# ESP32-Cam.net
KiCad netlist of a schematic drawn in Altium Designer
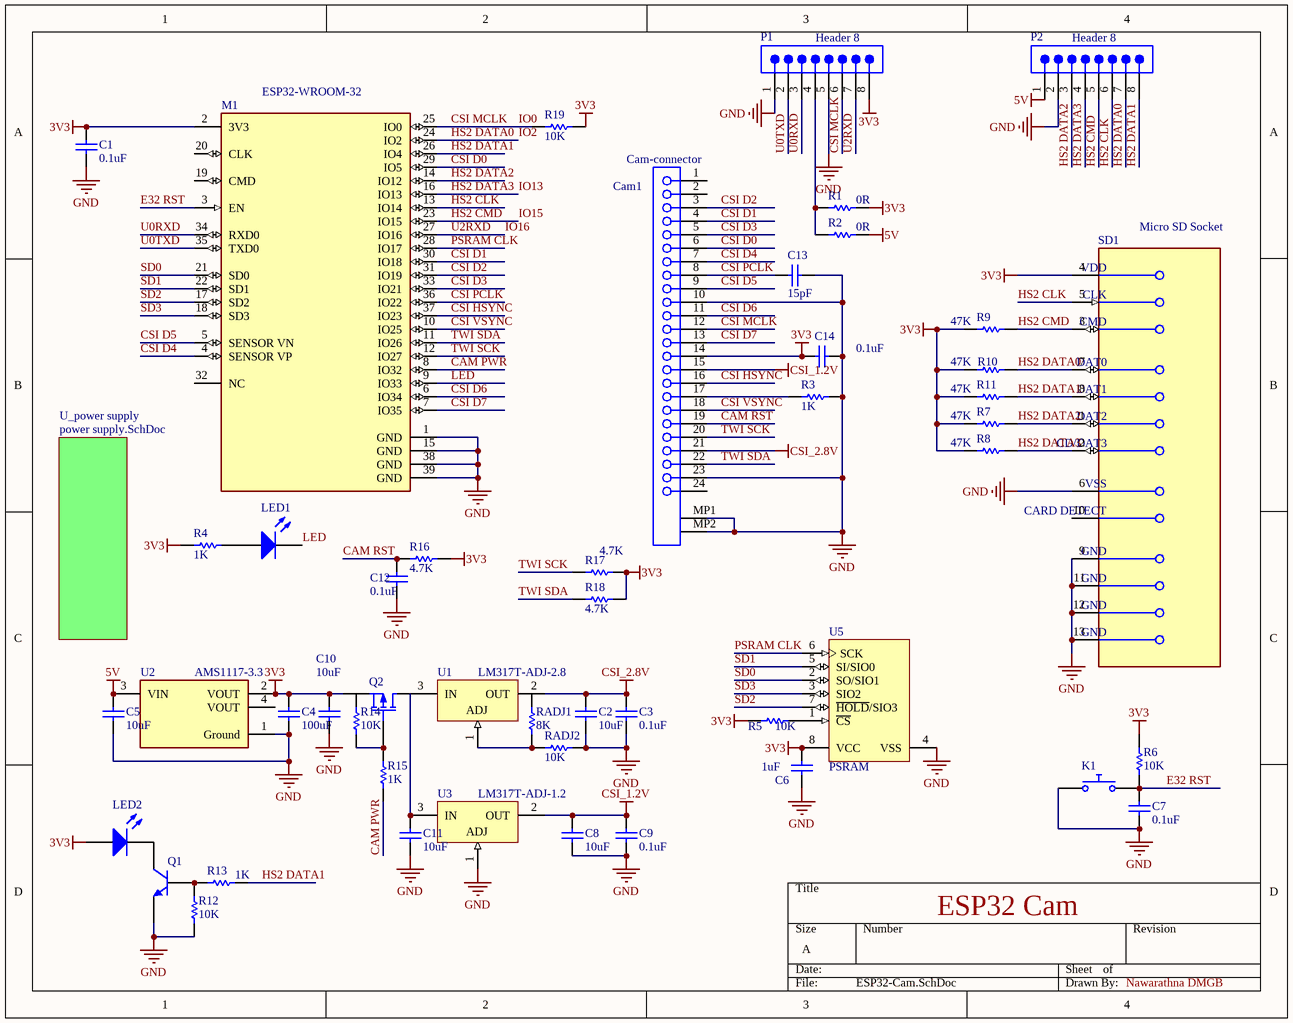
[diagram p0: ESP32-Cam.SchDoc]

(export (version "E")
  (design (tool "Eeschema 10.0.6"))
  (components
    (comp (ref "C1")
      (value "0.1uF")
      (description "Capacitor")
      (libsource (lib "Simulation Generic Components") (part "Capacitor"))
    )
    (comp (ref "C2")
      (value "10uF")
      (description "Capacitor")
      (libsource (lib "Simulation Generic Components") (part "Capacitor"))
    )
    (comp (ref "C3")
      (value "0.1uF")
      (description "Capacitor")
      (libsource (lib "Simulation Generic Components") (part "Capacitor"))
    )
    (comp (ref "C4")
      (value "100uF")
      (description "Capacitor")
      (libsource (lib "Simulation Generic Components") (part "Capacitor"))
    )
    (comp (ref "C5")
      (value "10uF")
      (description "Capacitor")
      (libsource (lib "Simulation Generic Components") (part "Capacitor"))
    )
    (comp (ref "C6")
      (value "1uF")
      (description "Capacitor")
      (libsource (lib "Simulation Generic Components") (part "Capacitor"))
    )
    (comp (ref "C7")
      (value "0.1uF")
      (description "Capacitor")
      (libsource (lib "Simulation Generic Components") (part "Capacitor"))
    )
    (comp (ref "C8")
      (value "10uF")
      (description "Capacitor")
      (libsource (lib "Simulation Generic Components") (part "Capacitor"))
    )
    (comp (ref "C9")
      (value "0.1uF")
      (description "Capacitor")
      (libsource (lib "Simulation Generic Components") (part "Capacitor"))
    )
    (comp (ref "C10")
      (value "10uF")
      (description "Capacitor")
      (libsource (lib "Simulation Generic Components") (part "Capacitor"))
    )
    (comp (ref "C11")
      (value "10uF")
      (description "Capacitor")
      (libsource (lib "Simulation Generic Components") (part "Capacitor"))
    )
    (comp (ref "C12")
      (value "0.1uF")
      (description "Capacitor")
      (libsource (lib "Simulation Generic Components") (part "Capacitor"))
    )
    (comp (ref "C13")
      (value "15pF")
      (description "Capacitor")
      (libsource (lib "Simulation Generic Components") (part "Capacitor"))
    )
    (comp (ref "C14")
      (value "0.1uF")
      (description "Capacitor")
      (libsource (lib "Simulation Generic Components") (part "Capacitor"))
    )
    (comp (ref "Cam1")
      (value "Cam-connector")
      (footprint "MOLX-52435-2471")
      (fields (field (name "PARTNUMBER") "52435-2471") (field (name "MANUFACTURER") "Molex"))
      (libsource (lib "Altium Content Vault") (part "MOLX-52435-2471"))
    )
    (comp (ref "K1")
      (value "Push Button Normally Opened")
      (libsource (lib "Simulation Generic Components") (part "Push Button NO"))
    )
    (comp (ref "LED1")
      (value "Light-Emitting Diode")
      (libsource (lib "Simulation Generic Components") (part "LED"))
    )
    (comp (ref "LED2")
      (value "Light-Emitting Diode")
      (libsource (lib "Simulation Generic Components") (part "LED"))
    )
    (comp (ref "M1")
      (value "ESP32-WROOM-32")
      (footprint "FP-ESP32-WROOM-32-MFG")
      (description "RX TXRX MOD WIFI SURFACE MOUNT")
      (libsource (lib "Altium Content Vault") (part "ee866abf0b6c51247b7f5cdebf2f250"))
    )
    (comp (ref "P1")
      (value "Header 8")
      (footprint "66200811122")
      (libsource (lib "Altium Content Vault") (part "Header_Male_1R_08P"))
    )
    (comp (ref "P2")
      (value "Header 8")
      (footprint "66200811122")
      (libsource (lib "Altium Content Vault") (part "Header_Male_1R_08P"))
    )
    (comp (ref "Q1")
      (value "Bipolar NPN 3 Pins Transistor Gummel-Poon Model")
      (libsource (lib "Simulation Generic Components") (part "BJT NPN_GP"))
    )
    (comp (ref "Q2")
      (value "P-channel Power MOSFET VDMOS Model")
      (libsource (lib "Simulation Generic Components") (part "MOSFET P-ch VDMOS"))
    )
    (comp (ref "R1")
      (value "0R")
      (description "Resistor")
      (libsource (lib "Simulation Generic Components") (part "Resistor"))
    )
    (comp (ref "R2")
      (value "0R")
      (description "Resistor")
      (libsource (lib "Simulation Generic Components") (part "Resistor"))
    )
    (comp (ref "R3")
      (value "1K")
      (description "Resistor")
      (libsource (lib "Simulation Generic Components") (part "Resistor"))
    )
    (comp (ref "R4")
      (value "1K")
      (description "Resistor")
      (libsource (lib "Simulation Generic Components") (part "Resistor"))
    )
    (comp (ref "R5")
      (value "10K")
      (description "Resistor")
      (libsource (lib "Simulation Generic Components") (part "Resistor"))
    )
    (comp (ref "R6")
      (value "10K")
      (description "Resistor")
      (libsource (lib "Simulation Generic Components") (part "Resistor"))
    )
    (comp (ref "R7")
      (value "47K")
      (description "Resistor")
      (libsource (lib "Simulation Generic Components") (part "Resistor"))
    )
    (comp (ref "R8")
      (value "47K")
      (description "Resistor")
      (libsource (lib "Simulation Generic Components") (part "Resistor"))
    )
    (comp (ref "R9")
      (value "47K")
      (description "Resistor")
      (libsource (lib "Simulation Generic Components") (part "Resistor"))
    )
    (comp (ref "R10")
      (value "47K")
      (description "Resistor")
      (libsource (lib "Simulation Generic Components") (part "Resistor"))
    )
    (comp (ref "R11")
      (value "47K")
      (description "Resistor")
      (libsource (lib "Simulation Generic Components") (part "Resistor"))
    )
    (comp (ref "R12")
      (value "10K")
      (description "Resistor")
      (libsource (lib "Simulation Generic Components") (part "Resistor"))
    )
    (comp (ref "R13")
      (value "1K")
      (description "Resistor")
      (libsource (lib "Simulation Generic Components") (part "Resistor"))
    )
    (comp (ref "R14")
      (value "10K")
      (description "Resistor")
      (libsource (lib "Simulation Generic Components") (part "Resistor"))
    )
    (comp (ref "R15")
      (value "1K")
      (description "Resistor")
      (libsource (lib "Simulation Generic Components") (part "Resistor"))
    )
    (comp (ref "R16")
      (value "4.7K")
      (description "Resistor")
      (libsource (lib "Simulation Generic Components") (part "Resistor"))
    )
    (comp (ref "R17")
      (value "4.7K")
      (description "Resistor")
      (libsource (lib "Simulation Generic Components") (part "Resistor"))
    )
    (comp (ref "R18")
      (value "4.7K")
      (description "Resistor")
      (libsource (lib "Simulation Generic Components") (part "Resistor"))
    )
    (comp (ref "R19")
      (value "10K")
      (description "Resistor")
      (libsource (lib "Simulation Generic Components") (part "Resistor"))
    )
    (comp (ref "RADJ1")
      (value "8K")
      (description "Resistor")
      (libsource (lib "Simulation Generic Components") (part "Resistor"))
    )
    (comp (ref "RADJ2")
      (value "10K")
      (description "Resistor")
      (libsource (lib "Simulation Generic Components") (part "Resistor"))
    )
    (comp (ref "SD1")
      (value "Micro SD Socket")
      (footprint "FP-DM3CS-SF-MFG")
      (description "CONN MICRO SD CARD HINGED TYPE")
      (libsource (lib "Altium Content Vault") (part "bac915de5305cfdd1ca301aae530106"))
    )
    (comp (ref "U1")
      (value "LM317T-ADJ-2.8")
      (footprint "TO-220")
      (description "1.5A, 1.2V to 37V Adjustable Voltage Regulator, 3-Pin TO-220")
      (libsource (lib "Altium Content Vault") (part "PM-REG-117-SIL3"))
    )
    (comp (ref "U2")
      (value "AMS1117-3.3")
      (footprint "FP-AMS1117-IPC_C")
      (description "LDO Voltage Regulators 1A, 3.3V")
      (fields
        (field (name "OCTOPART") "https://octopart.com/ams1117-3.3-advanced+monolithic+systems-25899300")
        (field (name "MANUFACTURER") "Advanced Monolithic Systems")
      )
      (libsource (lib "Altium Content Vault") (part "8bdbb5f8e77002000e30dd2845d0354"))
    )
    (comp (ref "U3")
      (value "LM317T-ADJ-1.2")
      (footprint "TO-220")
      (description "1.5A, 1.2V to 37V Adjustable Voltage Regulator, 3-Pin TO-220")
      (libsource (lib "Altium Content Vault") (part "PM-REG-117-SIL3"))
    )
    (comp (ref "U5")
      (value "PSRAM")
      (footprint "MCHP-SOIC-SN8_N")
      (fields (field (name "MANUFACTURER") "Microchip") (field (name "PARTNUMBER") "23LC512-I/SN"))
      (libsource (lib "Altium Content Vault") (part "MCHP-23A1024_512-LC1024_512-8"))
    )
  )
  (nets
    (net (code "1") (name "/CAM PWR") (class "Default")
      (node (ref "M1") (pin "8") (pinfunction "IO32_8") (pintype "bidirectional"))
      (node (ref "R15") (pin "2") (pinfunction "2_2") (pintype "passive"))
    )
    (net (code "2") (name "/CAM RST") (class "Default")
      (node (ref "C12") (pin "1") (pinfunction "1_1") (pintype "passive"))
      (node (ref "Cam1") (pin "19") (pinfunction "19_19") (pintype "passive"))
      (node (ref "R16") (pin "1") (pinfunction "1_1") (pintype "passive"))
    )
    (net (code "3") (name "/CSI D0") (class "Default")
      (node (ref "Cam1") (pin "6") (pinfunction "6_6") (pintype "passive"))
      (node (ref "M1") (pin "29") (pinfunction "IO5_29") (pintype "bidirectional"))
    )
    (net (code "4") (name "/CSI D1") (class "Default")
      (node (ref "Cam1") (pin "4") (pinfunction "4_4") (pintype "passive"))
      (node (ref "M1") (pin "30") (pinfunction "IO18_30") (pintype "bidirectional"))
    )
    (net (code "5") (name "/CSI D2") (class "Default")
      (node (ref "Cam1") (pin "3") (pinfunction "3_3") (pintype "passive"))
      (node (ref "M1") (pin "31") (pinfunction "IO19_31") (pintype "bidirectional"))
    )
    (net (code "6") (name "/CSI D3") (class "Default")
      (node (ref "Cam1") (pin "5") (pinfunction "5_5") (pintype "passive"))
      (node (ref "M1") (pin "33") (pinfunction "IO21_33") (pintype "bidirectional"))
    )
    (net (code "7") (name "/CSI D4") (class "Default")
      (node (ref "Cam1") (pin "7") (pinfunction "7_7") (pintype "passive"))
      (node (ref "M1") (pin "4") (pinfunction "SENSOR_VP_4") (pintype "bidirectional"))
    )
    (net (code "8") (name "/CSI D5") (class "Default")
      (node (ref "Cam1") (pin "9") (pinfunction "9_9") (pintype "passive"))
      (node (ref "M1") (pin "5") (pinfunction "SENSOR_VN_5") (pintype "bidirectional"))
    )
    (net (code "9") (name "/CSI D6") (class "Default")
      (node (ref "Cam1") (pin "11") (pinfunction "11_11") (pintype "passive"))
      (node (ref "M1") (pin "6") (pinfunction "IO34_6") (pintype "bidirectional"))
    )
    (net (code "10") (name "/CSI D7") (class "Default")
      (node (ref "Cam1") (pin "13") (pinfunction "13_13") (pintype "passive"))
      (node (ref "M1") (pin "7") (pinfunction "IO35_7") (pintype "bidirectional"))
    )
    (net (code "11") (name "/CSI HSYNC") (class "Default")
      (node (ref "Cam1") (pin "16") (pinfunction "16_16") (pintype "passive"))
      (node (ref "M1") (pin "37") (pinfunction "IO23_37") (pintype "bidirectional"))
    )
    (net (code "12") (name "/CSI MCLK") (class "Default")
      (node (ref "Cam1") (pin "12") (pinfunction "12_12") (pintype "passive"))
      (node (ref "M1") (pin "25") (pinfunction "IO0_25") (pintype "bidirectional"))
      (node (ref "P1") (pin "6") (pinfunction "6_6") (pintype "passive"))
      (node (ref "R19") (pin "1") (pinfunction "1_1") (pintype "passive"))
    )
    (net (code "13") (name "/CSI PCLK") (class "Default")
      (node (ref "C13") (pin "1") (pinfunction "1_1") (pintype "passive"))
      (node (ref "Cam1") (pin "8") (pinfunction "8_8") (pintype "passive"))
      (node (ref "M1") (pin "36") (pinfunction "IO22_36") (pintype "bidirectional"))
    )
    (net (code "14") (name "/CSI VSYNC") (class "Default")
      (node (ref "Cam1") (pin "18") (pinfunction "18_18") (pintype "passive"))
      (node (ref "M1") (pin "10") (pinfunction "IO25_10") (pintype "bidirectional"))
    )
    (net (code "15") (name "/E32 RST") (class "Default")
      (node (ref "C7") (pin "1") (pinfunction "1_1") (pintype "passive"))
      (node (ref "K1") (pin "2") (pinfunction "2_2") (pintype "passive"))
      (node (ref "M1") (pin "3") (pinfunction "EN_3") (pintype "input"))
      (node (ref "R6") (pin "2") (pinfunction "2_2") (pintype "passive"))
    )
    (net (code "16") (name "/HS2 CLK") (class "Default")
      (node (ref "M1") (pin "13") (pinfunction "IO14_13") (pintype "bidirectional"))
      (node (ref "P2") (pin "6") (pinfunction "6_6") (pintype "passive"))
      (node (ref "SD1") (pin "5") (pinfunction "CLK_5") (pintype "input"))
    )
    (net (code "17") (name "/HS2 CMD") (class "Default")
      (node (ref "M1") (pin "23") (pinfunction "IO15_23") (pintype "bidirectional"))
      (node (ref "P2") (pin "5") (pinfunction "5_5") (pintype "passive"))
      (node (ref "R9") (pin "2") (pinfunction "2_2") (pintype "passive"))
      (node (ref "SD1") (pin "3") (pinfunction "CMD_3") (pintype "bidirectional"))
    )
    (net (code "18") (name "/HS2 DATA0") (class "Default")
      (node (ref "M1") (pin "24") (pinfunction "IO2_24") (pintype "bidirectional"))
      (node (ref "P2") (pin "7") (pinfunction "7_7") (pintype "passive"))
      (node (ref "R10") (pin "2") (pinfunction "2_2") (pintype "passive"))
      (node (ref "SD1") (pin "7") (pinfunction "DAT0_7") (pintype "bidirectional"))
    )
    (net (code "19") (name "/HS2 DATA1") (class "Default")
      (node (ref "M1") (pin "26") (pinfunction "IO4_26") (pintype "bidirectional"))
      (node (ref "P2") (pin "8") (pinfunction "8_8") (pintype "passive"))
      (node (ref "R11") (pin "2") (pinfunction "2_2") (pintype "passive"))
      (node (ref "R13") (pin "1") (pinfunction "1_1") (pintype "passive"))
      (node (ref "SD1") (pin "8") (pinfunction "DAT1_8") (pintype "bidirectional"))
    )
    (net (code "20") (name "/HS2 DATA2") (class "Default")
      (node (ref "M1") (pin "14") (pinfunction "IO12_14") (pintype "bidirectional"))
      (node (ref "P2") (pin "3") (pinfunction "3_3") (pintype "passive"))
      (node (ref "R7") (pin "2") (pinfunction "2_2") (pintype "passive"))
      (node (ref "SD1") (pin "1") (pinfunction "DAT2_1") (pintype "bidirectional"))
    )
    (net (code "21") (name "/HS2 DATA3") (class "Default")
      (node (ref "M1") (pin "16") (pinfunction "IO13_16") (pintype "bidirectional"))
      (node (ref "P2") (pin "4") (pinfunction "4_4") (pintype "passive"))
      (node (ref "R8") (pin "2") (pinfunction "2_2") (pintype "passive"))
      (node (ref "SD1") (pin "2") (pinfunction "CD/DAT3_2") (pintype "bidirectional"))
    )
    (net (code "22") (name "/IO16") (class "Default")
      (node (ref "M1") (pin "27") (pinfunction "IO16_27") (pintype "bidirectional"))
      (node (ref "P1") (pin "7") (pinfunction "7_7") (pintype "passive"))
    )
    (net (code "23") (name "/LED") (class "Default")
      (node (ref "LED1") (pin "2") (pinfunction "K_2") (pintype "passive"))
      (node (ref "M1") (pin "9") (pinfunction "IO33_9") (pintype "bidirectional"))
    )
    (net (code "24") (name "/PSRAM CLK") (class "Default")
      (node (ref "M1") (pin "28") (pinfunction "IO17_28") (pintype "bidirectional"))
      (node (ref "U5") (pin "6") (pinfunction "SCK_6") (pintype "input"))
    )
    (net (code "25") (name "/SD0") (class "Default")
      (node (ref "M1") (pin "21") (pinfunction "SD0_21") (pintype "bidirectional"))
      (node (ref "U5") (pin "2") (pinfunction "SO/SIO1_2") (pintype "bidirectional"))
    )
    (net (code "26") (name "/SD1") (class "Default")
      (node (ref "M1") (pin "22") (pinfunction "SD1_22") (pintype "bidirectional"))
      (node (ref "U5") (pin "5") (pinfunction "SI/SIO0_5") (pintype "bidirectional"))
    )
    (net (code "27") (name "/SD2") (class "Default")
      (node (ref "M1") (pin "17") (pinfunction "SD2_17") (pintype "bidirectional"))
      (node (ref "U5") (pin "7") (pinfunction "~{HOLD}/SIO3_7") (pintype "bidirectional"))
    )
    (net (code "28") (name "/SD3") (class "Default")
      (node (ref "M1") (pin "18") (pinfunction "SD3_18") (pintype "bidirectional"))
      (node (ref "U5") (pin "3") (pinfunction "SIO2_3") (pintype "bidirectional"))
    )
    (net (code "29") (name "/TWI SCK") (class "Default")
      (node (ref "Cam1") (pin "20") (pinfunction "20_20") (pintype "passive"))
      (node (ref "M1") (pin "12") (pinfunction "IO27_12") (pintype "bidirectional"))
      (node (ref "R17") (pin "1") (pinfunction "1_1") (pintype "passive"))
    )
    (net (code "30") (name "/TWI SDA") (class "Default")
      (node (ref "Cam1") (pin "22") (pinfunction "22_22") (pintype "passive"))
      (node (ref "M1") (pin "11") (pinfunction "IO26_11") (pintype "bidirectional"))
      (node (ref "R18") (pin "1") (pinfunction "1_1") (pintype "passive"))
    )
    (net (code "31") (name "/U0RXD") (class "Default")
      (node (ref "M1") (pin "34") (pinfunction "RXD0_34") (pintype "bidirectional"))
      (node (ref "P1") (pin "3") (pinfunction "3_3") (pintype "passive"))
    )
    (net (code "32") (name "/U0TXD") (class "Default")
      (node (ref "M1") (pin "35") (pinfunction "TXD0_35") (pintype "bidirectional"))
      (node (ref "P1") (pin "2") (pinfunction "2_2") (pintype "passive"))
    )
    (net (code "33") (name "3V3") (class "Default")
      (node (ref "C1") (pin "1") (pinfunction "1_1") (pintype "passive"))
      (node (ref "C10") (pin "1") (pinfunction "1_1") (pintype "passive"))
      (node (ref "C14") (pin "1") (pinfunction "1_1") (pintype "passive"))
      (node (ref "C4") (pin "1") (pinfunction "1_1") (pintype "passive"))
      (node (ref "C6") (pin "1") (pinfunction "1_1") (pintype "passive"))
      (node (ref "Cam1") (pin "14") (pinfunction "14_14") (pintype "passive"))
      (node (ref "LED2") (pin "1") (pinfunction "A_1") (pintype "passive"))
      (node (ref "M1") (pin "2") (pinfunction "3V3_2") (pintype "power_in"))
      (node (ref "P1") (pin "8") (pinfunction "8_8") (pintype "passive"))
      (node (ref "Q2") (pin "3") (pinfunction "S_3") (pintype "passive"))
      (node (ref "R1") (pin "1") (pinfunction "1_1") (pintype "passive"))
      (node (ref "R10") (pin "1") (pinfunction "1_1") (pintype "passive"))
      (node (ref "R11") (pin "1") (pinfunction "1_1") (pintype "passive"))
      (node (ref "R16") (pin "2") (pinfunction "2_2") (pintype "passive"))
      (node (ref "R17") (pin "2") (pinfunction "2_2") (pintype "passive"))
      (node (ref "R18") (pin "2") (pinfunction "2_2") (pintype "passive"))
      (node (ref "R19") (pin "2") (pinfunction "2_2") (pintype "passive"))
      (node (ref "R4") (pin "1") (pinfunction "1_1") (pintype "passive"))
      (node (ref "R5") (pin "1") (pinfunction "1_1") (pintype "passive"))
      (node (ref "R6") (pin "1") (pinfunction "1_1") (pintype "passive"))
      (node (ref "R7") (pin "1") (pinfunction "1_1") (pintype "passive"))
      (node (ref "R8") (pin "1") (pinfunction "1_1") (pintype "passive"))
      (node (ref "R9") (pin "1") (pinfunction "1_1") (pintype "passive"))
      (node (ref "SD1") (pin "4") (pinfunction "VDD_4") (pintype "power_in"))
      (node (ref "U2") (pin "2") (pinfunction "VOUT_2") (pintype "passive"))
      (node (ref "U5") (pin "8") (pinfunction "VCC_8") (pintype "power_in"))
    )
    (net (code "34") (name "5V") (class "Default")
      (node (ref "C5") (pin "1") (pinfunction "1_1") (pintype "passive"))
      (node (ref "P2") (pin "1") (pinfunction "1_1") (pintype "passive"))
      (node (ref "R2") (pin "1") (pinfunction "1_1") (pintype "passive"))
      (node (ref "U2") (pin "3") (pinfunction "VIN_3") (pintype "power_in"))
    )
    (net (code "35") (name "CSI_1.2V") (class "Default")
      (node (ref "C8") (pin "1") (pinfunction "1_1") (pintype "passive"))
      (node (ref "C9") (pin "1") (pinfunction "1_1") (pintype "passive"))
      (node (ref "Cam1") (pin "15") (pinfunction "15_15") (pintype "passive"))
      (node (ref "U3") (pin "2") (pinfunction "OUT_2") (pintype "power_in"))
    )
    (net (code "36") (name "CSI_2.8V") (class "Default")
      (node (ref "C2") (pin "1") (pinfunction "1_1") (pintype "passive"))
      (node (ref "C3") (pin "1") (pinfunction "1_1") (pintype "passive"))
      (node (ref "Cam1") (pin "21") (pinfunction "21_21") (pintype "passive"))
      (node (ref "U1") (pin "2") (pinfunction "OUT_2") (pintype "power_in"))
    )
    (net (code "37") (name "GND") (class "Default")
      (node (ref "C1") (pin "2") (pinfunction "2_2") (pintype "passive"))
      (node (ref "C10") (pin "2") (pinfunction "2_2") (pintype "passive"))
      (node (ref "C11") (pin "2") (pinfunction "2_2") (pintype "passive"))
      (node (ref "C12") (pin "2") (pinfunction "2_2") (pintype "passive"))
      (node (ref "C13") (pin "2") (pinfunction "2_2") (pintype "passive"))
      (node (ref "C14") (pin "2") (pinfunction "2_2") (pintype "passive"))
      (node (ref "C2") (pin "2") (pinfunction "2_2") (pintype "passive"))
      (node (ref "C3") (pin "2") (pinfunction "2_2") (pintype "passive"))
      (node (ref "C4") (pin "2") (pinfunction "2_2") (pintype "passive"))
      (node (ref "C5") (pin "2") (pinfunction "2_2") (pintype "passive"))
      (node (ref "C6") (pin "2") (pinfunction "2_2") (pintype "passive"))
      (node (ref "C7") (pin "2") (pinfunction "2_2") (pintype "passive"))
      (node (ref "C8") (pin "2") (pinfunction "2_2") (pintype "passive"))
      (node (ref "C9") (pin "2") (pinfunction "2_2") (pintype "passive"))
      (node (ref "Cam1") (pin "10") (pinfunction "10_10") (pintype "passive"))
      (node (ref "Cam1") (pin "23") (pinfunction "23_23") (pintype "passive"))
      (node (ref "Cam1") (pin "MP1") (pinfunction "MP1_MP1") (pintype "passive"))
      (node (ref "Cam1") (pin "MP2") (pinfunction "MP2_MP2") (pintype "passive"))
      (node (ref "K1") (pin "1") (pinfunction "1_1") (pintype "passive"))
      (node (ref "M1") (pin "1") (pinfunction "GND_1") (pintype "power_in"))
      (node (ref "M1") (pin "15") (pinfunction "GND_15") (pintype "power_in"))
      (node (ref "M1") (pin "38") (pinfunction "GND_38") (pintype "power_in"))
      (node (ref "M1") (pin "39") (pinfunction "GND_39") (pintype "power_in"))
      (node (ref "P1") (pin "1") (pinfunction "1_1") (pintype "passive"))
      (node (ref "P1") (pin "5") (pinfunction "5_5") (pintype "passive"))
      (node (ref "P2") (pin "2") (pinfunction "2_2") (pintype "passive"))
      (node (ref "Q1") (pin "3") (pinfunction "E_3") (pintype "passive"))
      (node (ref "R12") (pin "2") (pinfunction "2_2") (pintype "passive"))
      (node (ref "R3") (pin "2") (pinfunction "2_2") (pintype "passive"))
      (node (ref "RADJ2") (pin "2") (pinfunction "2_2") (pintype "passive"))
      (node (ref "SD1") (pin "11") (pinfunction "GND_11") (pintype "power_in"))
      (node (ref "SD1") (pin "12") (pinfunction "GND_12") (pintype "power_in"))
      (node (ref "SD1") (pin "13") (pinfunction "GND_13") (pintype "power_in"))
      (node (ref "SD1") (pin "6") (pinfunction "VSS_6") (pintype "power_in"))
      (node (ref "SD1") (pin "9") (pinfunction "GND_9") (pintype "power_in"))
      (node (ref "U2") (pin "1") (pinfunction "Ground_1") (pintype "power_in"))
      (node (ref "U3") (pin "1") (pinfunction "ADJ_1") (pintype "input"))
      (node (ref "U5") (pin "4") (pinfunction "VSS_4") (pintype "power_in"))
    )
    (net (code "38") (name "Net-(Cam1-Pad17)") (class "Default")
      (node (ref "Cam1") (pin "17") (pinfunction "17_17") (pintype "passive"))
      (node (ref "R3") (pin "1") (pinfunction "1_1") (pintype "passive"))
    )
    (net (code "39") (name "Net-(LED1-A)") (class "Default")
      (node (ref "LED1") (pin "1") (pinfunction "A_1") (pintype "passive"))
      (node (ref "R4") (pin "2") (pinfunction "2_2") (pintype "passive"))
    )
    (net (code "40") (name "Net-(LED2-K)") (class "Default")
      (node (ref "LED2") (pin "2") (pinfunction "K_2") (pintype "passive"))
      (node (ref "Q1") (pin "1") (pinfunction "C_1") (pintype "passive"))
    )
    (net (code "41") (name "Net-(P1-Pad4)") (class "Default")
      (node (ref "P1") (pin "4") (pinfunction "4_4") (pintype "passive"))
      (node (ref "R1") (pin "2") (pinfunction "2_2") (pintype "passive"))
      (node (ref "R2") (pin "2") (pinfunction "2_2") (pintype "passive"))
    )
    (net (code "42") (name "Net-(Q1-B)") (class "Default")
      (node (ref "Q1") (pin "2") (pinfunction "B_2") (pintype "passive"))
      (node (ref "R12") (pin "1") (pinfunction "1_1") (pintype "passive"))
      (node (ref "R13") (pin "2") (pinfunction "2_2") (pintype "passive"))
    )
    (net (code "43") (name "Net-(Q2-G)") (class "Default")
      (node (ref "Q2") (pin "2") (pinfunction "G_2") (pintype "passive"))
      (node (ref "R14") (pin "2") (pinfunction "2_2") (pintype "passive"))
      (node (ref "R15") (pin "1") (pinfunction "1_1") (pintype "passive"))
    )
    (net (code "44") (name "Net-(U1-ADJ)") (class "Default")
      (node (ref "RADJ1") (pin "2") (pinfunction "2_2") (pintype "passive"))
      (node (ref "RADJ2") (pin "1") (pinfunction "1_1") (pintype "passive"))
      (node (ref "U1") (pin "1") (pinfunction "ADJ_1") (pintype "input"))
    )
    (net (code "45") (name "Net-(U1-IN)") (class "Default")
      (node (ref "C11") (pin "1") (pinfunction "1_1") (pintype "passive"))
      (node (ref "U1") (pin "3") (pinfunction "IN_3") (pintype "power_in"))
      (node (ref "U3") (pin "3") (pinfunction "IN_3") (pintype "power_in"))
    )
    (net (code "46") (name "Net-(U5-~{CS})") (class "Default")
      (node (ref "R5") (pin "2") (pinfunction "2_2") (pintype "passive"))
      (node (ref "U5") (pin "1") (pinfunction "~{CS}_1") (pintype "input"))
    )
    (net (code "47") (name "unconnected-(Cam1-Pad1)") (class "Default")
      (node (ref "Cam1") (pin "1") (pinfunction "1_1") (pintype "passive"))
    )
    (net (code "48") (name "unconnected-(Cam1-Pad2)") (class "Default")
      (node (ref "Cam1") (pin "2") (pinfunction "2_2") (pintype "passive"))
    )
    (net (code "49") (name "unconnected-(Cam1-Pad24)") (class "Default")
      (node (ref "Cam1") (pin "24") (pinfunction "24_24") (pintype "passive"))
    )
    (net (code "50") (name "unconnected-(M1-CLK-Pad20)") (class "Default")
      (node (ref "M1") (pin "20") (pinfunction "CLK_20") (pintype "bidirectional"))
    )
    (net (code "51") (name "unconnected-(M1-CMD-Pad19)") (class "Default")
      (node (ref "M1") (pin "19") (pinfunction "CMD_19") (pintype "bidirectional"))
    )
    (net (code "52") (name "unconnected-(M1-NC-Pad32)") (class "Default")
      (node (ref "M1") (pin "32") (pinfunction "NC_32") (pintype "passive"))
    )
    (net (code "53") (name "unconnected-(Q2-D-Pad1)") (class "Default")
      (node (ref "Q2") (pin "1") (pinfunction "D_1") (pintype "passive"))
    )
    (net (code "54") (name "unconnected-(R14-Pad1)") (class "Default")
      (node (ref "R14") (pin "1") (pinfunction "1_1") (pintype "passive"))
    )
    (net (code "55") (name "unconnected-(RADJ1-Pad1)") (class "Default")
      (node (ref "RADJ1") (pin "1") (pinfunction "1_1") (pintype "passive"))
    )
    (net (code "56") (name "unconnected-(SD1-CARD_DETECT-Pad10)") (class "Default")
      (node (ref "SD1") (pin "10") (pinfunction "CARD_DETECT_10") (pintype "passive"))
    )
    (net (code "57") (name "unconnected-(U2-VOUT-Pad4)") (class "Default")
      (node (ref "U2") (pin "4") (pinfunction "VOUT_4") (pintype "passive"))
    )
  )
)
